# pcbsrc.net
KiCad netlist of a schematic drawn in EasyEDA Pro
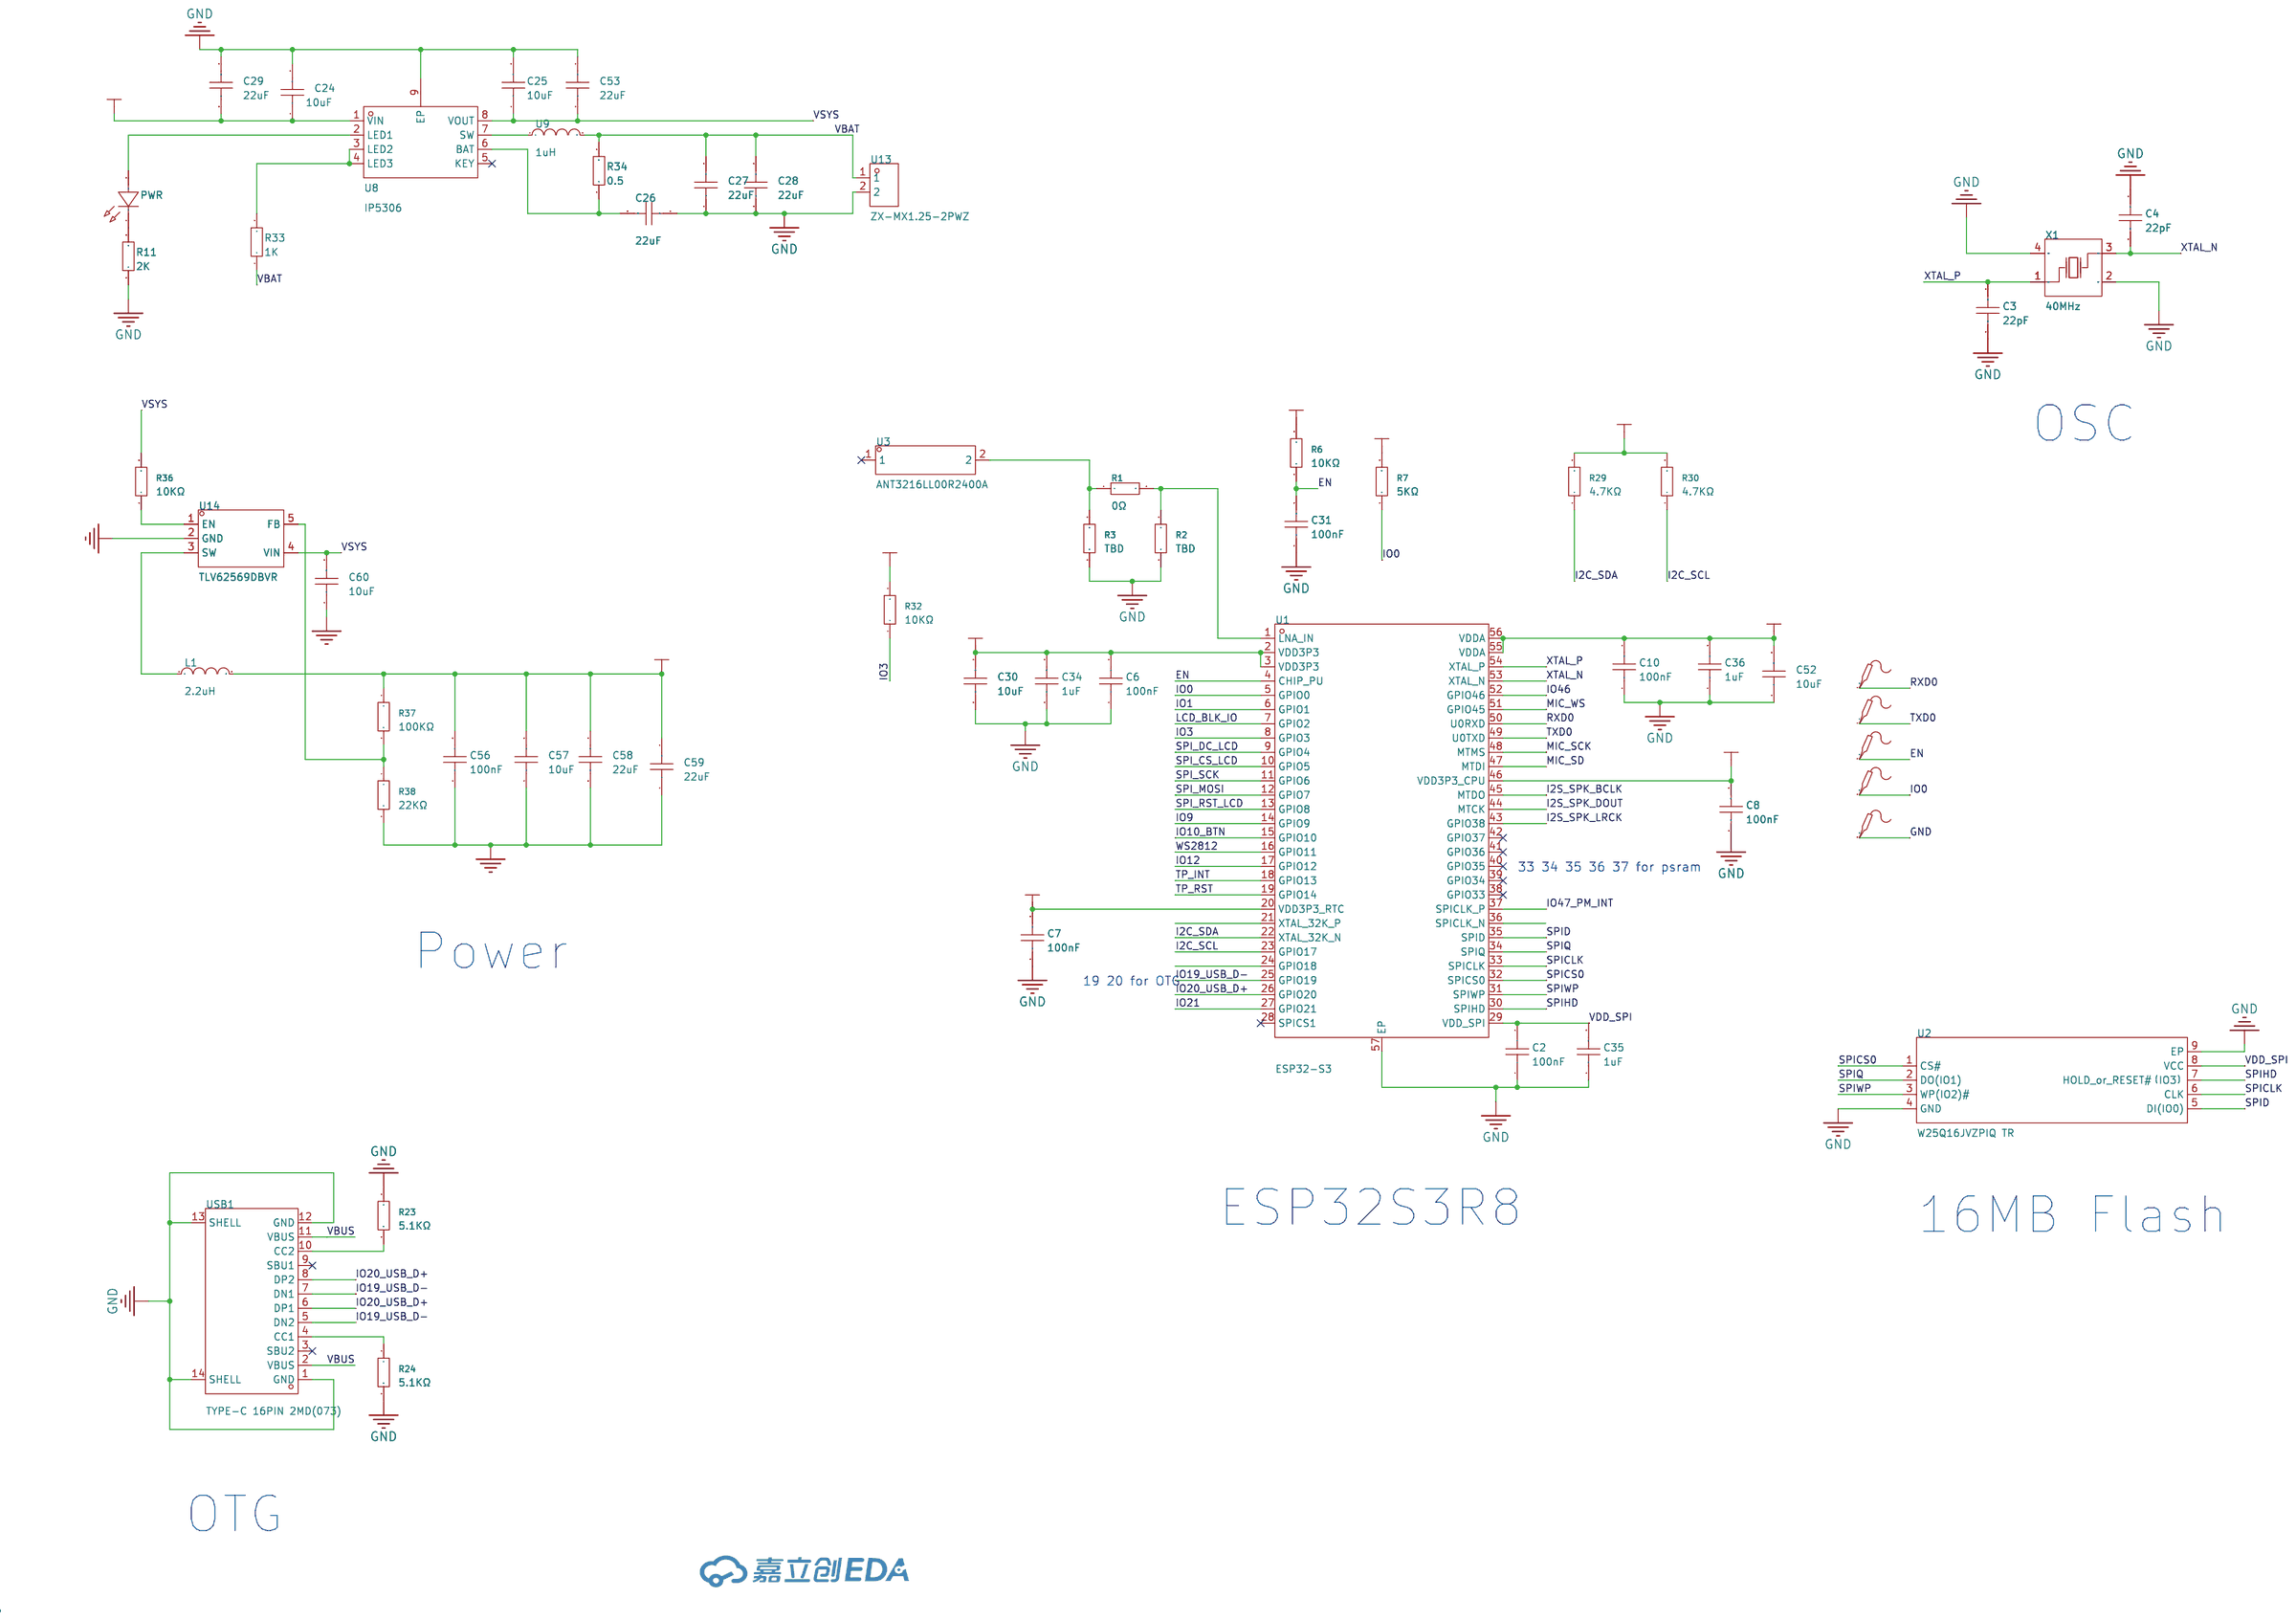
[diagram p0: esp32]
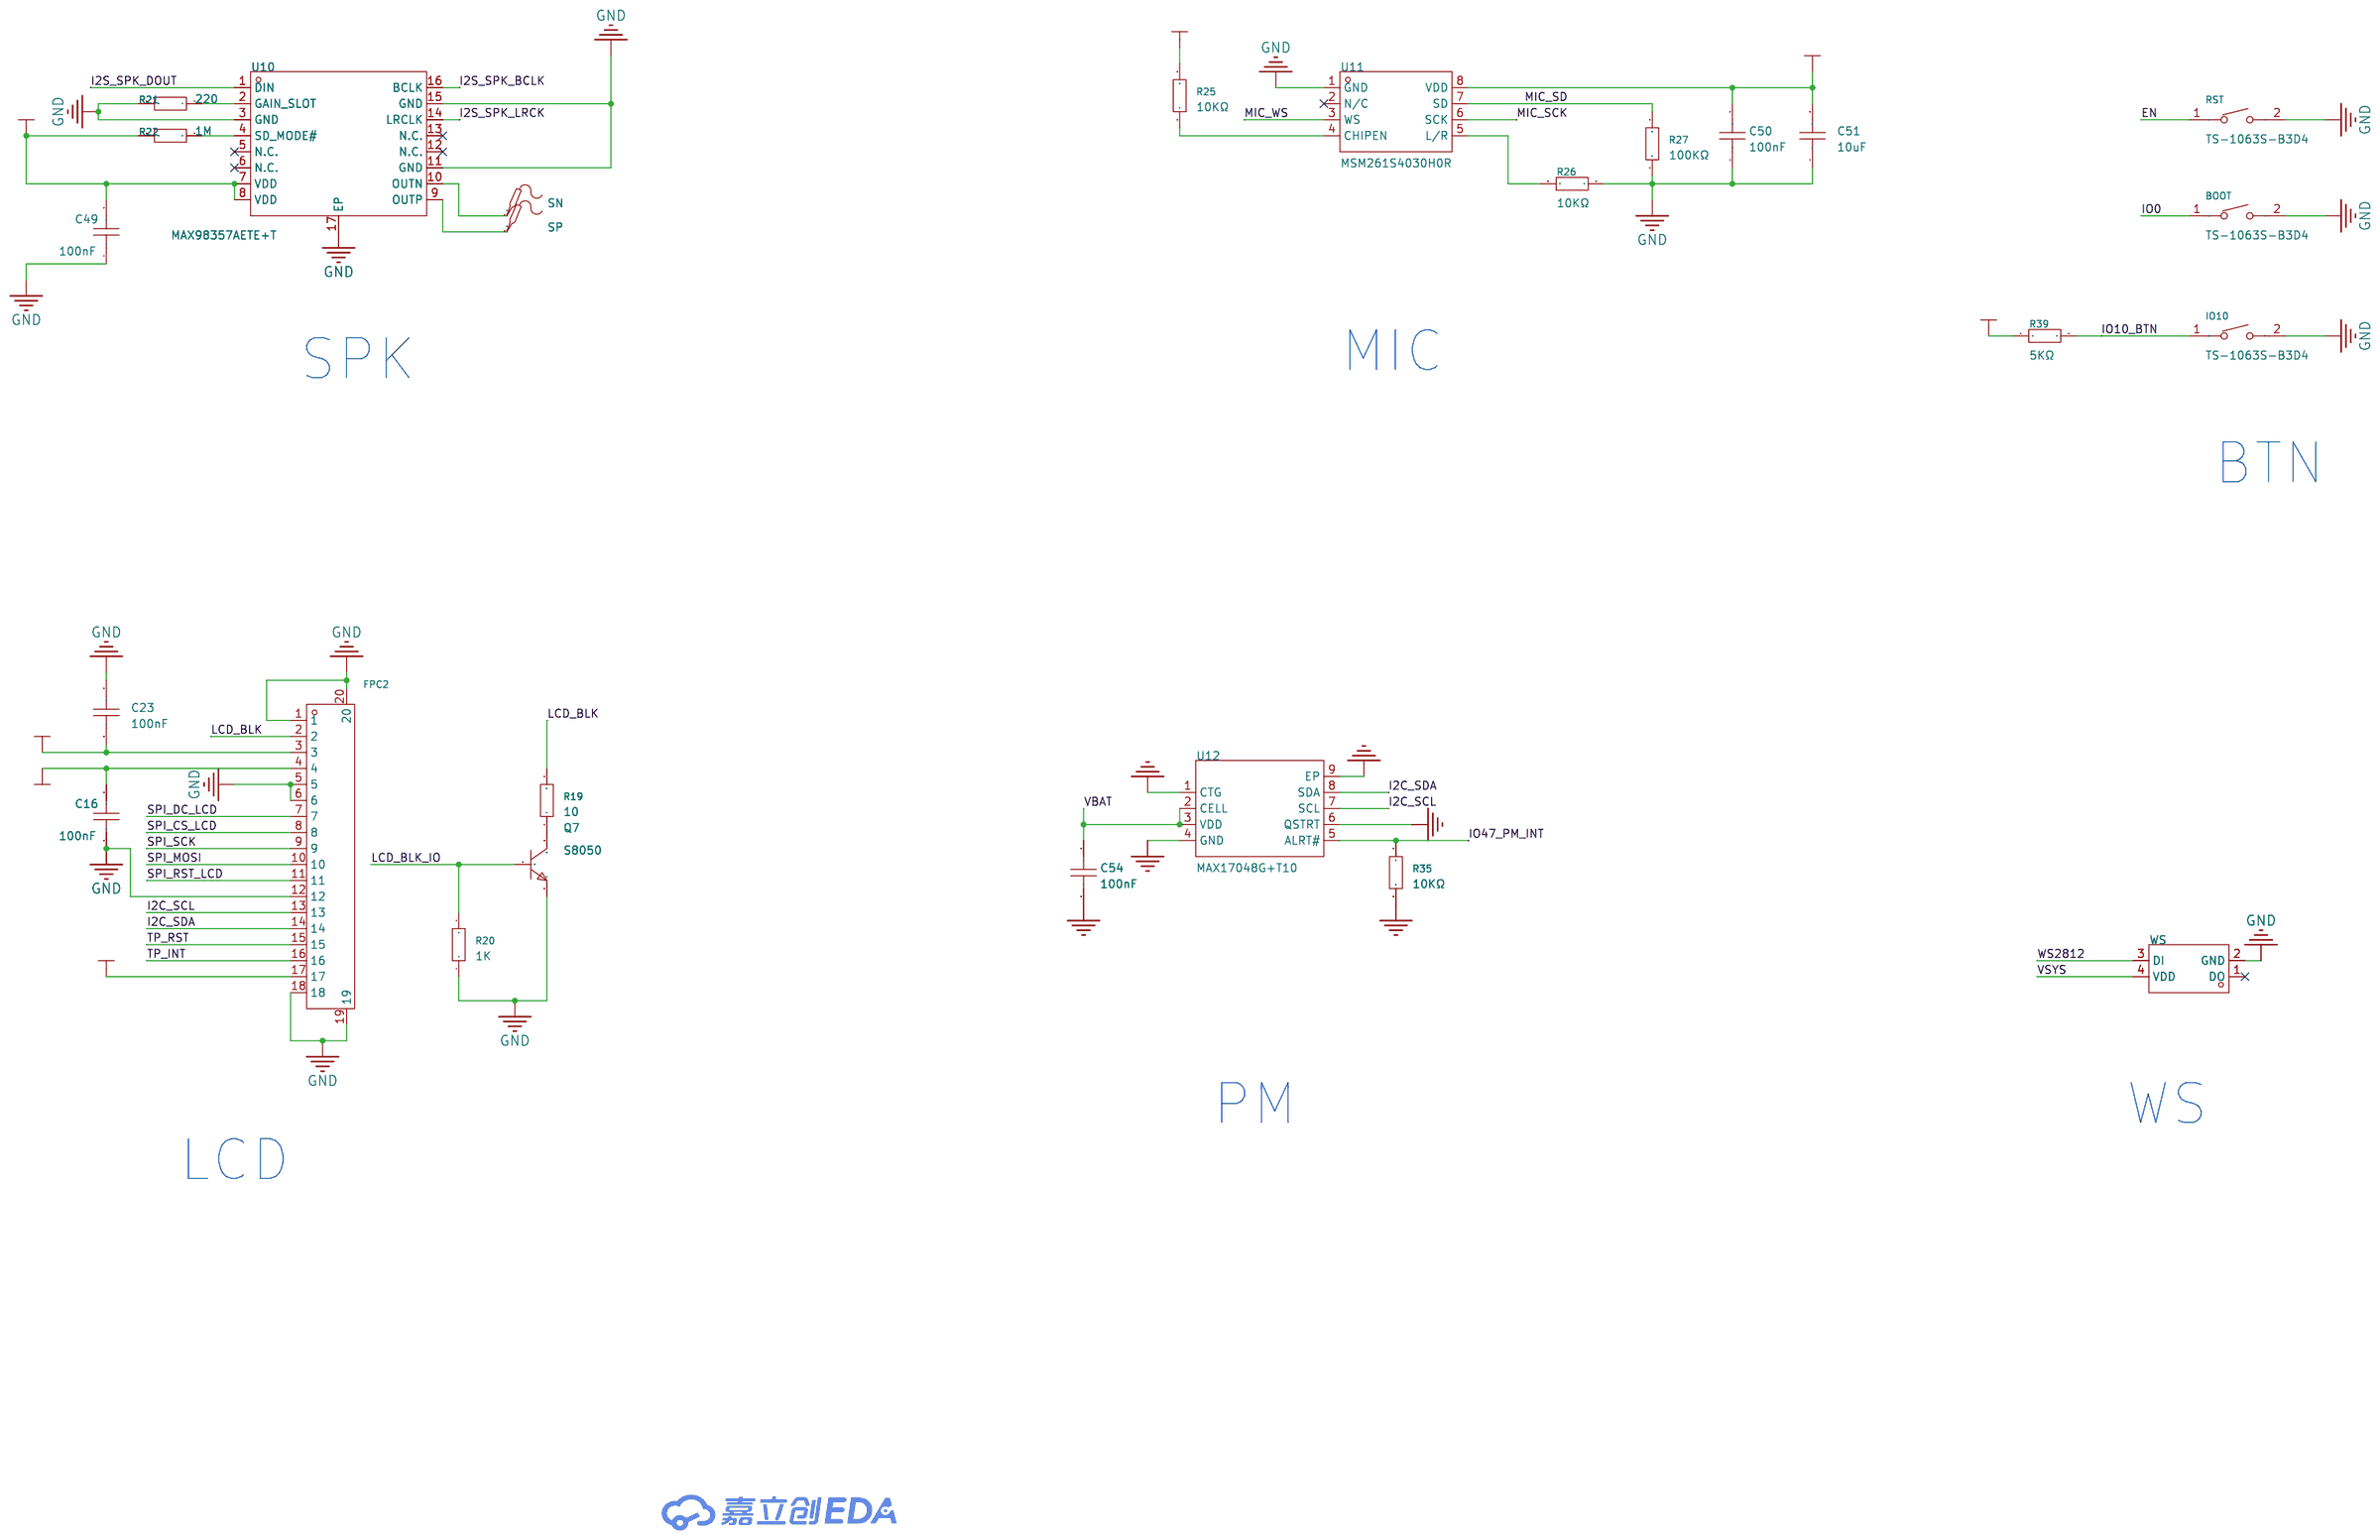
[diagram p1: peripheral]

(export (version "E")
  (design (tool "Eeschema 10.0.6"))
  (components
    (comp (ref "C2")
      (value "100nF")
      (footprint "easyedapro:C0402")
      (fields
        (field (name "Manufacturer Part") "CL05A105KA5NQNC")
        (field (name "Manufacturer") "SAMSUNG(三星)")
      )
      (libsource (lib "easyedapro") (part "CL05A105KA5NQNC"))
    )
    (comp (ref "C3")
      (value "22pF")
      (footprint "easyedapro:C0402")
      (fields
        (field (name "Manufacturer Part") "CL05A105KA5NQNC")
        (field (name "Manufacturer") "SAMSUNG(三星)")
      )
      (libsource (lib "easyedapro") (part "CL05A105KA5NQNC"))
    )
    (comp (ref "C4")
      (value "22pF")
      (footprint "easyedapro:C0402")
      (fields
        (field (name "Manufacturer Part") "CL05A105KA5NQNC")
        (field (name "Manufacturer") "SAMSUNG(三星)")
      )
      (libsource (lib "easyedapro") (part "CL05A105KA5NQNC"))
    )
    (comp (ref "C6")
      (value "100nF")
      (footprint "easyedapro:C0402")
      (fields
        (field (name "Manufacturer Part") "CL05A105KA5NQNC")
        (field (name "Manufacturer") "SAMSUNG(三星)")
      )
      (libsource (lib "easyedapro") (part "CL05A105KA5NQNC"))
    )
    (comp (ref "C7")
      (value "100nF")
      (footprint "easyedapro:C0402")
      (fields
        (field (name "Manufacturer Part") "CL05A105KA5NQNC")
        (field (name "Manufacturer") "SAMSUNG(三星)")
      )
      (libsource (lib "easyedapro") (part "CL05A105KA5NQNC"))
    )
    (comp (ref "C8")
      (value "100nF")
      (footprint "easyedapro:C0402")
      (fields
        (field (name "Manufacturer Part") "CL05A105KA5NQNC")
        (field (name "Manufacturer") "SAMSUNG(三星)")
      )
      (libsource (lib "easyedapro") (part "CL05A105KA5NQNC"))
    )
    (comp (ref "C10")
      (value "100nF")
      (footprint "easyedapro:C0402")
      (fields
        (field (name "Manufacturer Part") "CL05A105KA5NQNC")
        (field (name "Manufacturer") "SAMSUNG(三星)")
      )
      (libsource (lib "easyedapro") (part "CL05A105KA5NQNC"))
    )
    (comp (ref "C24")
      (value "10uF")
      (footprint "easyedapro:C0603")
      (description "容值:10uF;精度:±10%;额定电压:10V;材质(温度系数):X5R;")
      (fields
        (field (name "Manufacturer Part") "CGA0603X5R106K100JT")
        (field (name "Manufacturer") "HRE(芯声)")
      )
      (libsource (lib "easyedapro") (part "CGA0603X5R106K100JT"))
    )
    (comp (ref "C25")
      (value "10uF")
      (footprint "easyedapro:C0603")
      (description "容值:10uF;精度:±10%;额定电压:10V;材质(温度系数):X5R;")
      (fields
        (field (name "Manufacturer Part") "CGA0603X5R106K100JT")
        (field (name "Manufacturer") "HRE(芯声)")
      )
      (libsource (lib "easyedapro") (part "CGA0603X5R106K100JT"))
    )
    (comp (ref "C26")
      (value "22uF")
      (footprint "easyedapro:C0603")
      (description "容值:10uF;精度:±10%;额定电压:10V;材质(温度系数):X5R;")
      (fields
        (field (name "Manufacturer Part") "CGA0603X5R106K100JT")
        (field (name "Manufacturer") "HRE(芯声)")
      )
      (libsource (lib "easyedapro") (part "CGA0603X5R106K100JT"))
    )
    (comp (ref "C27")
      (value "22uF")
      (footprint "easyedapro:C0603")
      (description "容值:10uF;精度:±10%;额定电压:10V;材质(温度系数):X5R;")
      (fields
        (field (name "Manufacturer Part") "CGA0603X5R106K100JT")
        (field (name "Manufacturer") "HRE(芯声)")
      )
      (libsource (lib "easyedapro") (part "CGA0603X5R106K100JT"))
    )
    (comp (ref "C28")
      (value "22uF")
      (footprint "easyedapro:C0603")
      (description "容值:10uF;精度:±10%;额定电压:10V;材质(温度系数):X5R;")
      (fields
        (field (name "Manufacturer Part") "CGA0603X5R106K100JT")
        (field (name "Manufacturer") "HRE(芯声)")
      )
      (libsource (lib "easyedapro") (part "CGA0603X5R106K100JT"))
    )
    (comp (ref "C29")
      (value "22uF")
      (footprint "easyedapro:C0603")
      (description "容值:10uF;精度:±10%;额定电压:10V;材质(温度系数):X5R;")
      (fields
        (field (name "Manufacturer Part") "CGA0603X5R106K100JT")
        (field (name "Manufacturer") "HRE(芯声)")
      )
      (libsource (lib "easyedapro") (part "CGA0603X5R106K100JT"))
    )
    (comp (ref "C30")
      (value "10uF")
      (footprint "easyedapro:C0603")
      (description "Capacitance:10uF Tolerance:±10% Tolerance:±10% Voltage Rating:10V Temperature Coefficient:X5R")
      (fields
        (field (name "Manufacturer Part") "CGA0603X5R106K100JT")
        (field (name "Manufacturer") "HRE(芯声)")
      )
      (libsource (lib "") (part "CGA0603X5R106K100JT_1"))
    )
    (comp (ref "C31")
      (value "100nF")
      (footprint "easyedapro:C0402")
      (fields
        (field (name "Manufacturer Part") "CL05A105KA5NQNC")
        (field (name "Manufacturer") "SAMSUNG(三星)")
      )
      (libsource (lib "easyedapro") (part "CL05A105KA5NQNC"))
    )
    (comp (ref "C34")
      (value "1uF")
      (footprint "easyedapro:C0402")
      (fields
        (field (name "Manufacturer Part") "CL05A105KA5NQNC")
        (field (name "Manufacturer") "SAMSUNG(三星)")
      )
      (libsource (lib "easyedapro") (part "CL05A105KA5NQNC"))
    )
    (comp (ref "C35")
      (value "1uF")
      (footprint "easyedapro:C0402")
      (fields
        (field (name "Manufacturer Part") "CL05A105KA5NQNC")
        (field (name "Manufacturer") "SAMSUNG(三星)")
      )
      (libsource (lib "easyedapro") (part "CL05A105KA5NQNC"))
    )
    (comp (ref "C36")
      (value "1uF")
      (footprint "easyedapro:C0402")
      (fields
        (field (name "Manufacturer Part") "CL05A105KA5NQNC")
        (field (name "Manufacturer") "SAMSUNG(三星)")
      )
      (libsource (lib "easyedapro") (part "CL05A105KA5NQNC"))
    )
    (comp (ref "C52")
      (value "10uF")
      (footprint "easyedapro:C0603")
      (description "Capacitance:10uF Tolerance:±10% Tolerance:±10% Voltage Rating:10V Temperature Coefficient:X5R")
      (fields
        (field (name "Manufacturer Part") "CGA0603X5R106K100JT")
        (field (name "Manufacturer") "HRE(芯声)")
      )
      (libsource (lib "") (part "CGA0603X5R106K100JT_1"))
    )
    (comp (ref "C53")
      (value "22uF")
      (footprint "easyedapro:C0603")
      (description "容值:10uF;精度:±10%;额定电压:10V;材质(温度系数):X5R;")
      (fields
        (field (name "Manufacturer Part") "CGA0603X5R106K100JT")
        (field (name "Manufacturer") "HRE(芯声)")
      )
      (libsource (lib "easyedapro") (part "CGA0603X5R106K100JT"))
    )
    (comp (ref "C56")
      (value "100nF")
      (footprint "easyedapro:C0402")
      (fields
        (field (name "Manufacturer Part") "CL05A105KA5NQNC")
        (field (name "Manufacturer") "SAMSUNG(三星)")
      )
      (libsource (lib "easyedapro") (part "CL05A105KA5NQNC"))
    )
    (comp (ref "C57")
      (value "10uF")
      (footprint "easyedapro:C0603")
      (description "Capacitance:10uF Tolerance:±10% Tolerance:±10% Voltage Rating:10V Temperature Coefficient:X5R")
      (fields
        (field (name "Manufacturer Part") "CGA0603X5R106K100JT")
        (field (name "Manufacturer") "HRE(芯声)")
      )
      (libsource (lib "") (part "CGA0603X5R106K100JT_1"))
    )
    (comp (ref "C58")
      (value "22uF")
      (footprint "easyedapro:C0603")
      (description "容值:10uF;精度:±10%;额定电压:10V;材质(温度系数):X5R;")
      (fields
        (field (name "Manufacturer Part") "CGA0603X5R106K100JT")
        (field (name "Manufacturer") "HRE(芯声)")
      )
      (libsource (lib "easyedapro") (part "CGA0603X5R106K100JT"))
    )
    (comp (ref "C59")
      (value "22uF")
      (footprint "easyedapro:C0603")
      (description "容值:10uF;精度:±10%;额定电压:10V;材质(温度系数):X5R;")
      (fields
        (field (name "Manufacturer Part") "CGA0603X5R106K100JT")
        (field (name "Manufacturer") "HRE(芯声)")
      )
      (libsource (lib "easyedapro") (part "CGA0603X5R106K100JT"))
    )
    (comp (ref "C60")
      (value "10uF")
      (footprint "easyedapro:C0603")
      (description "Capacitance:10uF Tolerance:±10% Tolerance:±10% Voltage Rating:10V Temperature Coefficient:X5R")
      (fields
        (field (name "Manufacturer Part") "CGA0603X5R106K100JT")
        (field (name "Manufacturer") "HRE(芯声)")
      )
      (libsource (lib "") (part "CGA0603X5R106K100JT_1"))
    )
    (comp (ref "EN")
      (value "~")
      (footprint "easyedapro:Test-Point-0.5mm")
      (description "Test Point 测试点")
      (libsource (lib "easyedapro") (part "Test-Point"))
    )
    (comp (ref "IO0")
      (value "~")
      (footprint "easyedapro:Test-Point-0.5mm")
      (description "Test Point 测试点")
      (libsource (lib "easyedapro") (part "Test-Point"))
    )
    (comp (ref "IO11")
      (value "~")
      (footprint "easyedapro:Test-Point-0.5mm")
      (description "Test Point 测试点")
      (libsource (lib "easyedapro") (part "Test-Point"))
    )
    (comp (ref "L1")
      (value "2.2uH")
      (footprint "easyedapro:IND-SMD_L4.0-W4.0_LQH44PN2R2MP0L")
      (description "电感值:2.2uH;精度:±20%;额定电流:3.4A;饱和电流(Isat):3.4A;")
      (fields (field (name "Manufacturer Part") "SMNR4020-2.2UH") (field (name "Manufacturer") "SXN(顺翔诺)"))
      (libsource (lib "easyedapro") (part "SMNR4020-2.2UH"))
    )
    (comp (ref "PWR")
      (value "XL-1608SURC-06")
      (footprint "easyedapro:LED0603-RD_RED")
      (description "发光颜色:红色;功率:55mW;正向电流:25mA;主波长:617nm~621nm;透镜颜色:无色透明透镜;色温:-;发光角度:120°;载带方式:正贴;工作温度:-30°C~+85°C;")
      (fields (field (name "Manufacturer") "XINGLIGHT(成兴光)"))
      (libsource (lib "easyedapro") (part "XL-1608SURC-06"))
    )
    (comp (ref "R1")
      (value "0Ω")
      (footprint "easyedapro:R0402")
      (fields
        (field (name "Manufacturer Part") "0402WGF0000TCE")
        (field (name "Manufacturer") "UNI-ROYAL(厚声)")
      )
      (libsource (lib "easyedapro") (part "0402WGF0000TCE"))
    )
    (comp (ref "R2")
      (value "TBD")
      (footprint "easyedapro:R0402")
      (fields
        (field (name "Manufacturer Part") "0402WGF0000TCE")
        (field (name "Manufacturer") "UNI-ROYAL(厚声)")
      )
      (libsource (lib "easyedapro") (part "0402WGF0000TCE"))
    )
    (comp (ref "R3")
      (value "TBD")
      (footprint "easyedapro:R0402")
      (fields
        (field (name "Manufacturer Part") "0402WGF0000TCE")
        (field (name "Manufacturer") "UNI-ROYAL(厚声)")
      )
      (libsource (lib "easyedapro") (part "0402WGF0000TCE"))
    )
    (comp (ref "R6")
      (value "10KΩ")
      (footprint "easyedapro:R0402")
      (fields
        (field (name "Manufacturer Part") "0402WGF0000TCE")
        (field (name "Manufacturer") "UNI-ROYAL(厚声)")
      )
      (libsource (lib "easyedapro") (part "0402WGF0000TCE"))
    )
    (comp (ref "R7")
      (value "5KΩ")
      (footprint "easyedapro:R0402")
      (fields
        (field (name "Manufacturer Part") "0402WGF0000TCE")
        (field (name "Manufacturer") "UNI-ROYAL(厚声)")
      )
      (libsource (lib "easyedapro") (part "0402WGF0000TCE"))
    )
    (comp (ref "R11")
      (value "2K")
      (footprint "easyedapro:R0402")
      (description "电阻类型:厚膜电阻;阻值:470Ω;精度:±1%;功率:62.5mW;最大工作电压:50V;温度系数:±100ppm/°C;")
      (fields
        (field (name "Manufacturer Part") "0402WGF4700TCE")
        (field (name "Manufacturer") "UNI-ROYAL(厚声)")
      )
      (libsource (lib "easyedapro") (part "0402WGF4700TCE"))
    )
    (comp (ref "R23")
      (value "5.1KΩ")
      (footprint "easyedapro:R0402")
      (fields
        (field (name "Manufacturer Part") "0402WGF0000TCE")
        (field (name "Manufacturer") "UNI-ROYAL(厚声)")
      )
      (libsource (lib "easyedapro") (part "0402WGF0000TCE"))
    )
    (comp (ref "R24")
      (value "5.1KΩ")
      (footprint "easyedapro:R0402")
      (fields
        (field (name "Manufacturer Part") "0402WGF0000TCE")
        (field (name "Manufacturer") "UNI-ROYAL(厚声)")
      )
      (libsource (lib "easyedapro") (part "0402WGF0000TCE"))
    )
    (comp (ref "R29")
      (value "4.7KΩ")
      (footprint "easyedapro:R0402")
      (fields
        (field (name "Manufacturer Part") "0402WGF0000TCE")
        (field (name "Manufacturer") "UNI-ROYAL(厚声)")
      )
      (libsource (lib "easyedapro") (part "0402WGF0000TCE"))
    )
    (comp (ref "R30")
      (value "4.7KΩ")
      (footprint "easyedapro:R0402")
      (fields
        (field (name "Manufacturer Part") "0402WGF0000TCE")
        (field (name "Manufacturer") "UNI-ROYAL(厚声)")
      )
      (libsource (lib "easyedapro") (part "0402WGF0000TCE"))
    )
    (comp (ref "R32")
      (value "10KΩ")
      (footprint "easyedapro:R0402")
      (fields
        (field (name "Manufacturer Part") "0402WGF0000TCE")
        (field (name "Manufacturer") "UNI-ROYAL(厚声)")
      )
      (libsource (lib "easyedapro") (part "0402WGF0000TCE"))
    )
    (comp (ref "R33")
      (value "1K")
      (footprint "easyedapro:R0402")
      (description "电阻类型:厚膜电阻;阻值:470Ω;精度:±1%;功率:62.5mW;最大工作电压:50V;温度系数:±100ppm/°C;")
      (fields
        (field (name "Manufacturer Part") "0402WGF4700TCE")
        (field (name "Manufacturer") "UNI-ROYAL(厚声)")
      )
      (libsource (lib "easyedapro") (part "0402WGF4700TCE"))
    )
    (comp (ref "R34")
      (value "1K")
      (footprint "easyedapro:R0402")
      (description "电阻类型:厚膜电阻;阻值:470Ω;精度:±1%;功率:62.5mW;最大工作电压:50V;温度系数:±100ppm/°C;")
      (fields
        (field (name "Manufacturer Part") "0402WGF4700TCE")
        (field (name "Manufacturer") "UNI-ROYAL(厚声)")
      )
      (libsource (lib "easyedapro") (part "0402WGF4700TCE"))
    )
    (comp (ref "R36")
      (value "10KΩ")
      (footprint "easyedapro:R0402")
      (fields
        (field (name "Manufacturer Part") "0402WGF0000TCE")
        (field (name "Manufacturer") "UNI-ROYAL(厚声)")
      )
      (libsource (lib "easyedapro") (part "0402WGF0000TCE"))
    )
    (comp (ref "R37")
      (value "100KΩ")
      (footprint "easyedapro:R0402")
      (fields
        (field (name "Manufacturer Part") "0402WGF0000TCE")
        (field (name "Manufacturer") "UNI-ROYAL(厚声)")
      )
      (libsource (lib "easyedapro") (part "0402WGF0000TCE"))
    )
    (comp (ref "R38")
      (value "22KΩ")
      (footprint "easyedapro:R0402")
      (fields
        (field (name "Manufacturer Part") "0402WGF0000TCE")
        (field (name "Manufacturer") "UNI-ROYAL(厚声)")
      )
      (libsource (lib "easyedapro") (part "0402WGF0000TCE"))
    )
    (comp (ref "RXD0")
      (value "~")
      (footprint "easyedapro:Test-Point-0.5mm")
      (description "Test Point 测试点")
      (libsource (lib "easyedapro") (part "Test-Point"))
    )
    (comp (ref "TXD0")
      (value "~")
      (footprint "easyedapro:Test-Point-0.5mm")
      (description "Test Point 测试点")
      (libsource (lib "easyedapro") (part "Test-Point"))
    )
    (comp (ref "U1")
      (value "ESP32-S3")
      (footprint "easyedapro:QFN-56_L7.0-W7.0-P0.40-TL-EP4.0")
      (fields (field (name "Manufacturer") "ESPRESSIF(乐鑫)"))
      (libsource (lib "easyedapro") (part "ESP32-S3"))
    )
    (comp (ref "U2")
      (value "W25Q16JVZPIQ TR")
      (footprint "easyedapro:WSON-8_L6.0-W5.0-P1.27-BL-EP")
      (fields (field (name "Manufacturer") "WINBOND(华邦)"))
      (libsource (lib "easyedapro") (part "W25Q16JVZPIQ TR"))
    )
    (comp (ref "U3")
      (value "ANT3216LL00R2400A")
      (footprint "easyedapro:ANT-SMD_L3.2-W1.6")
      (fields (field (name "Manufacturer") "YAGEO(国巨)"))
      (libsource (lib "easyedapro") (part "ANT3216LL00R2400A"))
    )
    (comp (ref "U8")
      (value "IP5306")
      (footprint "easyedapro:ESOP-8_L4.9-W3.9-P1.27-LS6.0-BL-EP")
      (fields (field (name "Manufacturer") "INJOINIC(英集芯)"))
      (libsource (lib "easyedapro") (part "IP5306"))
    )
    (comp (ref "U9")
      (value "1uH")
      (footprint "easyedapro:IND-SMD_L2.5-W2.0_YXNAQ252010-3R3M")
      (fields (field (name "Manufacturer Part") "IND\\L2.5XW"))
      (libsource (lib "easyedapro") (part "IND{backslash}L2.5XW"))
    )
    (comp (ref "U13")
      (value "ZX-MX1.25-2PWZ")
      (footprint "easyedapro:CONN-TH_2P-P1.25_ZX-MX1.25-2PWZ")
      (fields (field (name "Manufacturer") "Megastar(兆星)"))
      (libsource (lib "easyedapro") (part "ZX-MX1.25-2PWZ"))
    )
    (comp (ref "U14")
      (value "TLV62569DBVR")
      (footprint "easyedapro:SOT-23-5_L3.0-W1.7-P0.95-LS2.8-BR")
      (description "功能类型:降压型;输出类型:可调;工作电压:2.5V~5.5V;输出电压:600mV~5.5V;输出电流:2A;")
      (fields (field (name "Manufacturer") "TI(德州仪器)"))
      (libsource (lib "easyedapro") (part "TLV62569DBVR"))
    )
    (comp (ref "USB1")
      (value "TYPE-C 16PIN 2MD(073)")
      (footprint "easyedapro:USB-C-SMD_TYPE-C-6PIN-2MD-073")
      (fields (field (name "Manufacturer") "SHOU HAN(首韩)"))
      (libsource (lib "easyedapro") (part "TYPE-C 16PIN 2MD(073)"))
    )
    (comp (ref "X1")
      (value "40MHz")
      (footprint "easyedapro:OSC-SMD_4P-L3.2-W2.5-BL_SIT8008BI")
      (fields (field (name "Manufacturer Part") "X322540MPB4SI") (field (name "Manufacturer") "YXC(扬兴晶振)"))
      (libsource (lib "easyedapro") (part "X322540MPB4SI"))
    )
    (comp (ref "BOOT")
      (value "TS-1063S-B3D4")
      (footprint "easyedapro:KEY-SMD_L3.0-W2.5-LS4.0_TS-1603S")
      (fields (field (name "Manufacturer") "Yuandi(元迪)"))
      (libsource (lib "easyedapro") (part "TS-1063S-B3D4"))
    )
    (comp (ref "C16")
      (value "100nF")
      (footprint "easyedapro:C0402")
      (fields
        (field (name "Manufacturer Part") "CL05B104KO5NNNC")
        (field (name "Manufacturer") "SAMSUNG(三星)")
      )
      (libsource (lib "easyedapro") (part "CL05B104KO5NNNC"))
    )
    (comp (ref "C23")
      (value "100nF")
      (footprint "easyedapro:C0402")
      (fields
        (field (name "Manufacturer Part") "CL05B104KO5NNNC")
        (field (name "Manufacturer") "SAMSUNG(三星)")
      )
      (libsource (lib "easyedapro") (part "CL05B104KO5NNNC"))
    )
    (comp (ref "C49")
      (value "100nF")
      (footprint "easyedapro:C0402")
      (fields
        (field (name "Manufacturer Part") "CL05B104KO5NNNC")
        (field (name "Manufacturer") "SAMSUNG(三星)")
      )
      (libsource (lib "easyedapro") (part "CL05B104KO5NNNC"))
    )
    (comp (ref "C50")
      (value "100nF")
      (footprint "easyedapro:C0402")
      (fields
        (field (name "Manufacturer Part") "CL05A105KA5NQNC")
        (field (name "Manufacturer") "SAMSUNG(三星)")
      )
      (libsource (lib "easyedapro") (part "CL05A105KA5NQNC"))
    )
    (comp (ref "C51")
      (value "10uF")
      (footprint "easyedapro:C0603")
      (description "Capacitance:10uF Tolerance:±10% Tolerance:±10% Voltage Rating:10V Temperature Coefficient:X5R")
      (fields
        (field (name "Manufacturer Part") "CGA0603X5R106K100JT")
        (field (name "Manufacturer") "HRE(芯声)")
      )
      (libsource (lib "easyedapro") (part "CGA0603X5R106K100JT"))
    )
    (comp (ref "C54")
      (value "100nF")
      (footprint "easyedapro:C0402")
      (fields
        (field (name "Manufacturer Part") "CL05A105KA5NQNC")
        (field (name "Manufacturer") "SAMSUNG(三星)")
      )
      (libsource (lib "easyedapro") (part "CL05A105KA5NQNC"))
    )
    (comp (ref "FPC2")
      (value "FPC-05F-18PH20")
      (footprint "easyedapro:FPC-SMD_18P-P0.50_FPC-05F-18PH20")
      (fields (field (name "Manufacturer") "XUNPU(讯普)"))
      (libsource (lib "easyedapro") (part "FPC-05F-18PH20"))
    )
    (comp (ref "IO10")
      (value "TS-1063S-B3D4")
      (footprint "easyedapro:KEY-SMD_L3.0-W2.5-LS4.0_TS-1603S")
      (fields (field (name "Manufacturer") "Yuandi(元迪)"))
      (libsource (lib "easyedapro") (part "TS-1063S-B3D4"))
    )
    (comp (ref "Q7")
      (value "S8050")
      (footprint "easyedapro:SOT-23-3_L2.9-W1.3-P1.90-LS2.3-BR")
      (fields (field (name "Manufacturer") "宏嘉诚"))
      (libsource (lib "easyedapro") (part "S8050_C20069125"))
    )
    (comp (ref "R19")
      (value "10")
      (footprint "easyedapro:R0402")
      (fields
        (field (name "Manufacturer Part") "0402WGF4700TCE")
        (field (name "Manufacturer") "UNI-ROYAL(厚声)")
      )
      (libsource (lib "easyedapro") (part "0402WGF4700TCE"))
    )
    (comp (ref "R20")
      (value "1K")
      (footprint "easyedapro:R0402")
      (fields
        (field (name "Manufacturer Part") "0402WGF4700TCE")
        (field (name "Manufacturer") "UNI-ROYAL(厚声)")
      )
      (libsource (lib "easyedapro") (part "0402WGF4700TCE"))
    )
    (comp (ref "R21")
      (value "220")
      (footprint "easyedapro:R0402")
      (fields
        (field (name "Manufacturer Part") "0402WGF4700TCE")
        (field (name "Manufacturer") "UNI-ROYAL(厚声)")
      )
      (libsource (lib "easyedapro") (part "0402WGF4700TCE"))
    )
    (comp (ref "R22")
      (value "1M")
      (footprint "easyedapro:R0402")
      (fields
        (field (name "Manufacturer Part") "0402WGF4700TCE")
        (field (name "Manufacturer") "UNI-ROYAL(厚声)")
      )
      (libsource (lib "easyedapro") (part "0402WGF4700TCE"))
    )
    (comp (ref "R25")
      (value "10KΩ")
      (footprint "easyedapro:R0402")
      (fields
        (field (name "Manufacturer Part") "0402WGF0000TCE")
        (field (name "Manufacturer") "UNI-ROYAL(厚声)")
      )
      (libsource (lib "easyedapro") (part "0402WGF0000TCE"))
    )
    (comp (ref "R26")
      (value "10KΩ")
      (footprint "easyedapro:R0402")
      (fields
        (field (name "Manufacturer Part") "0402WGF0000TCE")
        (field (name "Manufacturer") "UNI-ROYAL(厚声)")
      )
      (libsource (lib "easyedapro") (part "0402WGF0000TCE"))
    )
    (comp (ref "R27")
      (value "100KΩ")
      (footprint "easyedapro:R0402")
      (fields
        (field (name "Manufacturer Part") "0402WGF0000TCE")
        (field (name "Manufacturer") "UNI-ROYAL(厚声)")
      )
      (libsource (lib "easyedapro") (part "0402WGF0000TCE"))
    )
    (comp (ref "R35")
      (value "10KΩ")
      (footprint "easyedapro:R0402")
      (fields
        (field (name "Manufacturer Part") "0402WGF0000TCE")
        (field (name "Manufacturer") "UNI-ROYAL(厚声)")
      )
      (libsource (lib "easyedapro") (part "0402WGF0000TCE"))
    )
    (comp (ref "R39")
      (value "5KΩ")
      (footprint "easyedapro:R0402")
      (fields
        (field (name "Manufacturer Part") "0402WGF0000TCE")
        (field (name "Manufacturer") "UNI-ROYAL(厚声)")
      )
      (libsource (lib "easyedapro") (part "0402WGF0000TCE"))
    )
    (comp (ref "RST")
      (value "TS-1063S-B3D4")
      (footprint "easyedapro:KEY-SMD_L3.0-W2.5-LS4.0_TS-1603S")
      (fields (field (name "Manufacturer") "Yuandi(元迪)"))
      (libsource (lib "easyedapro") (part "TS-1063S-B3D4"))
    )
    (comp (ref "SN")
      (value "~")
      (footprint "easyedapro:Test-Point-0.5mm")
      (description "Test Point 测试点")
      (libsource (lib "easyedapro") (part "Test-Point"))
    )
    (comp (ref "SP")
      (value "~")
      (footprint "easyedapro:Test-Point-0.5mm")
      (description "Test Point 测试点")
      (libsource (lib "easyedapro") (part "Test-Point"))
    )
    (comp (ref "U10")
      (value "MAX98357AETE+T")
      (footprint "easyedapro:TQFN-16_L3.0-W3.0-P0.50-BL-EP1.5")
      (fields (field (name "Manufacturer") "ADI(亚德诺)/MAXIM(美信)"))
      (libsource (lib "easyedapro") (part "MAX98357AETE+T"))
    )
    (comp (ref "U11")
      (value "MSM261S4030H0R")
      (footprint "easyedapro:MIC-SMD_8P-L4.0-W3.0-P1.00-BR")
      (fields (field (name "Manufacturer") "MEMS(敏芯微)"))
      (libsource (lib "easyedapro") (part "MSM261S4030H0R"))
    )
    (comp (ref "U12")
      (value "MAX17048G+T10")
      (footprint "easyedapro:TDFN-8_L2.0-W2.0-P0.50-BL-EP1.2")
      (description "工作电压:2.5V~4.5V;电池类型:锂离子/聚合物;电池节数:1;")
      (fields (field (name "Manufacturer") "ADI(亚德诺)/MAXIM(美信)"))
      (libsource (lib "easyedapro") (part "MAX17048G+T10"))
    )
    (comp (ref "WS")
      (value "XL-2020RGBC-WS2812B")
      (footprint "easyedapro:LED-SMD_4P-L2.0-W2.0-BR-1")
      (fields (field (name "Manufacturer") "XINGLIGHT(成兴光)"))
      (libsource (lib "easyedapro") (part "XL-2020RGBC-WS2812B"))
    )
  )
  (nets
    (net (code "1") (name "EN") (class "Default")
      (node (ref "C31") (pin "2") (pinfunction "2_2") (pintype "unspecified"))
      (node (ref "EN") (pin "1") (pinfunction "1_1") (pintype "input"))
      (node (ref "R6") (pin "1") (pinfunction "1_1") (pintype "input"))
      (node (ref "RST") (pin "1") (pinfunction "1_1") (pintype "input"))
      (node (ref "U1") (pin "4") (pinfunction "CHIP_PU_4") (pintype "unspecified"))
    )
    (net (code "2") (name "GND") (class "Default")
      (node (ref "BOOT") (pin "2") (pinfunction "2_2") (pintype "input"))
      (node (ref "C10") (pin "1") (pinfunction "1_1") (pintype "unspecified"))
      (node (ref "C16") (pin "1") (pinfunction "1_1") (pintype "unspecified"))
      (node (ref "C2") (pin "1") (pinfunction "1_1") (pintype "unspecified"))
      (node (ref "C23") (pin "1") (pinfunction "1_1") (pintype "unspecified"))
      (node (ref "C24") (pin "2") (pinfunction "2_2") (pintype "unspecified"))
      (node (ref "C25") (pin "2") (pinfunction "2_2") (pintype "unspecified"))
      (node (ref "C26") (pin "1") (pinfunction "1_1") (pintype "unspecified"))
      (node (ref "C27") (pin "2") (pinfunction "2_2") (pintype "unspecified"))
      (node (ref "C28") (pin "2") (pinfunction "2_2") (pintype "unspecified"))
      (node (ref "C29") (pin "1") (pinfunction "1_1") (pintype "unspecified"))
      (node (ref "C3") (pin "1") (pinfunction "1_1") (pintype "unspecified"))
      (node (ref "C30") (pin "1") (pinfunction "1_1") (pintype "unspecified"))
      (node (ref "C31") (pin "1") (pinfunction "1_1") (pintype "unspecified"))
      (node (ref "C34") (pin "1") (pinfunction "1_1") (pintype "unspecified"))
      (node (ref "C35") (pin "1") (pinfunction "1_1") (pintype "unspecified"))
      (node (ref "C36") (pin "1") (pinfunction "1_1") (pintype "unspecified"))
      (node (ref "C4") (pin "2") (pinfunction "2_2") (pintype "unspecified"))
      (node (ref "C49") (pin "1") (pinfunction "1_1") (pintype "unspecified"))
      (node (ref "C50") (pin "1") (pinfunction "1_1") (pintype "unspecified"))
      (node (ref "C51") (pin "1") (pinfunction "1_1") (pintype "unspecified"))
      (node (ref "C52") (pin "1") (pinfunction "1_1") (pintype "unspecified"))
      (node (ref "C53") (pin "1") (pinfunction "1_1") (pintype "unspecified"))
      (node (ref "C54") (pin "1") (pinfunction "1_1") (pintype "unspecified"))
      (node (ref "C56") (pin "1") (pinfunction "1_1") (pintype "unspecified"))
      (node (ref "C57") (pin "1") (pinfunction "1_1") (pintype "unspecified"))
      (node (ref "C58") (pin "2") (pinfunction "2_2") (pintype "unspecified"))
      (node (ref "C59") (pin "2") (pinfunction "2_2") (pintype "unspecified"))
      (node (ref "C6") (pin "1") (pinfunction "1_1") (pintype "unspecified"))
      (node (ref "C60") (pin "1") (pinfunction "1_1") (pintype "unspecified"))
      (node (ref "C7") (pin "1") (pinfunction "1_1") (pintype "unspecified"))
      (node (ref "C8") (pin "1") (pinfunction "1_1") (pintype "unspecified"))
      (node (ref "FPC2") (pin "1") (pinfunction "1_1") (pintype "input"))
      (node (ref "FPC2") (pin "12") (pinfunction "12_12") (pintype "input"))
      (node (ref "FPC2") (pin "18") (pinfunction "18_18") (pintype "input"))
      (node (ref "FPC2") (pin "19") (pinfunction "19_19") (pintype "input"))
      (node (ref "FPC2") (pin "20") (pinfunction "20_20") (pintype "input"))
      (node (ref "FPC2") (pin "5") (pinfunction "5_5") (pintype "input"))
      (node (ref "FPC2") (pin "6") (pinfunction "6_6") (pintype "input"))
      (node (ref "IO10") (pin "2") (pinfunction "2_2") (pintype "input"))
      (node (ref "IO11") (pin "1") (pinfunction "1_1") (pintype "input"))
      (node (ref "Q7") (pin "2") (pinfunction "E_2") (pintype "input"))
      (node (ref "R11") (pin "1") (pinfunction "1_1") (pintype "input"))
      (node (ref "R2") (pin "1") (pinfunction "1_1") (pintype "input"))
      (node (ref "R20") (pin "1") (pinfunction "1_1") (pintype "input"))
      (node (ref "R21") (pin "2") (pinfunction "2_2") (pintype "input"))
      (node (ref "R23") (pin "1") (pinfunction "1_1") (pintype "input"))
      (node (ref "R24") (pin "2") (pinfunction "2_2") (pintype "input"))
      (node (ref "R26") (pin "1") (pinfunction "1_1") (pintype "input"))
      (node (ref "R27") (pin "2") (pinfunction "2_2") (pintype "input"))
      (node (ref "R3") (pin "1") (pinfunction "1_1") (pintype "input"))
      (node (ref "R35") (pin "2") (pinfunction "2_2") (pintype "input"))
      (node (ref "R38") (pin "2") (pinfunction "2_2") (pintype "input"))
      (node (ref "RST") (pin "2") (pinfunction "2_2") (pintype "input"))
      (node (ref "U1") (pin "57") (pinfunction "EP_57") (pintype "unspecified"))
      (node (ref "U10") (pin "11") (pinfunction "GND_11") (pintype "unspecified"))
      (node (ref "U10") (pin "15") (pinfunction "GND_15") (pintype "unspecified"))
      (node (ref "U10") (pin "17") (pinfunction "EP_17") (pintype "unspecified"))
      (node (ref "U10") (pin "3") (pinfunction "GND_3") (pintype "unspecified"))
      (node (ref "U11") (pin "1") (pinfunction "GND_1") (pintype "unspecified"))
      (node (ref "U12") (pin "1") (pinfunction "CTG_1") (pintype "unspecified"))
      (node (ref "U12") (pin "4") (pinfunction "GND_4") (pintype "unspecified"))
      (node (ref "U12") (pin "6") (pinfunction "QSTRT_6") (pintype "unspecified"))
      (node (ref "U12") (pin "9") (pinfunction "EP_9") (pintype "unspecified"))
      (node (ref "U13") (pin "2") (pinfunction "2_2") (pintype "unspecified"))
      (node (ref "U14") (pin "2") (pinfunction "GND_2") (pintype "unspecified"))
      (node (ref "U2") (pin "4") (pinfunction "GND_4") (pintype "unspecified"))
      (node (ref "U2") (pin "9") (pinfunction "EP_9") (pintype "unspecified"))
      (node (ref "U8") (pin "9") (pinfunction "EP_9") (pintype "unspecified"))
      (node (ref "USB1") (pin "1") (pinfunction "GND_1") (pintype "unspecified"))
      (node (ref "USB1") (pin "12") (pinfunction "GND_12") (pintype "unspecified"))
      (node (ref "USB1") (pin "13") (pinfunction "SHELL_13") (pintype "unspecified"))
      (node (ref "USB1") (pin "14") (pinfunction "SHELL_14") (pintype "unspecified"))
      (node (ref "WS") (pin "2") (pinfunction "GND_2") (pintype "unspecified"))
      (node (ref "X1") (pin "2") (pinfunction "GND_2") (pintype "unspecified"))
      (node (ref "X1") (pin "4") (pinfunction "GND_4") (pintype "unspecified"))
    )
    (net (code "3") (name "I2C_SCL") (class "Default")
      (node (ref "FPC2") (pin "13") (pinfunction "13_13") (pintype "input"))
      (node (ref "R30") (pin "1") (pinfunction "1_1") (pintype "input"))
      (node (ref "U1") (pin "23") (pinfunction "GPIO17_23") (pintype "unspecified"))
      (node (ref "U12") (pin "7") (pinfunction "SCL_7") (pintype "unspecified"))
    )
    (net (code "4") (name "I2C_SDA") (class "Default")
      (node (ref "FPC2") (pin "14") (pinfunction "14_14") (pintype "input"))
      (node (ref "R29") (pin "1") (pinfunction "1_1") (pintype "input"))
      (node (ref "U1") (pin "22") (pinfunction "XTAL_32K_N_22") (pintype "unspecified"))
      (node (ref "U12") (pin "8") (pinfunction "SDA_8") (pintype "unspecified"))
    )
    (net (code "5") (name "I2S_SPK_BCLK") (class "Default")
      (node (ref "U1") (pin "45") (pinfunction "MTDO_45") (pintype "unspecified"))
      (node (ref "U10") (pin "16") (pinfunction "BCLK_16") (pintype "unspecified"))
    )
    (net (code "6") (name "I2S_SPK_DOUT") (class "Default")
      (node (ref "U1") (pin "44") (pinfunction "MTCK_44") (pintype "unspecified"))
      (node (ref "U10") (pin "1") (pinfunction "DIN_1") (pintype "unspecified"))
    )
    (net (code "7") (name "I2S_SPK_LRCK") (class "Default")
      (node (ref "U1") (pin "43") (pinfunction "GPIO38_43") (pintype "unspecified"))
      (node (ref "U10") (pin "14") (pinfunction "LRCLK_14") (pintype "unspecified"))
    )
    (net (code "8") (name "IO0") (class "Default")
      (node (ref "BOOT") (pin "1") (pinfunction "1_1") (pintype "input"))
      (node (ref "IO0") (pin "1") (pinfunction "1_1") (pintype "input"))
      (node (ref "R7") (pin "1") (pinfunction "1_1") (pintype "input"))
      (node (ref "U1") (pin "5") (pinfunction "GPIO0_5") (pintype "unspecified"))
    )
    (net (code "9") (name "IO1") (class "Default")
      (node (ref "U1") (pin "6") (pinfunction "GPIO1_6") (pintype "unspecified"))
    )
    (net (code "10") (name "IO3") (class "Default")
      (node (ref "R32") (pin "1") (pinfunction "1_1") (pintype "input"))
      (node (ref "U1") (pin "8") (pinfunction "GPIO3_8") (pintype "unspecified"))
    )
    (net (code "11") (name "IO9") (class "Default")
      (node (ref "U1") (pin "14") (pinfunction "GPIO9_14") (pintype "unspecified"))
    )
    (net (code "12") (name "IO10_BTN") (class "Default")
      (node (ref "IO10") (pin "1") (pinfunction "1_1") (pintype "input"))
      (node (ref "R39") (pin "1") (pinfunction "1_1") (pintype "input"))
      (node (ref "U1") (pin "15") (pinfunction "GPIO10_15") (pintype "unspecified"))
    )
    (net (code "13") (name "IO12") (class "Default")
      (node (ref "U1") (pin "17") (pinfunction "GPIO12_17") (pintype "unspecified"))
    )
    (net (code "14") (name "IO19_USB_D-") (class "Default")
      (node (ref "U1") (pin "25") (pinfunction "GPIO19_25") (pintype "unspecified"))
      (node (ref "USB1") (pin "5") (pinfunction "DN2_5") (pintype "unspecified"))
      (node (ref "USB1") (pin "7") (pinfunction "DN1_7") (pintype "unspecified"))
    )
    (net (code "15") (name "IO20_USB_D+") (class "Default")
      (node (ref "U1") (pin "26") (pinfunction "GPIO20_26") (pintype "unspecified"))
      (node (ref "USB1") (pin "6") (pinfunction "DP1_6") (pintype "unspecified"))
      (node (ref "USB1") (pin "8") (pinfunction "DP2_8") (pintype "unspecified"))
    )
    (net (code "16") (name "IO21") (class "Default")
      (node (ref "U1") (pin "27") (pinfunction "GPIO21_27") (pintype "unspecified"))
    )
    (net (code "17") (name "IO46") (class "Default")
      (node (ref "U1") (pin "52") (pinfunction "GPIO46_52") (pintype "unspecified"))
    )
    (net (code "18") (name "IO47_PM_INT") (class "Default")
      (node (ref "R35") (pin "1") (pinfunction "1_1") (pintype "input"))
      (node (ref "U1") (pin "37") (pinfunction "SPICLK_P_37") (pintype "unspecified"))
      (node (ref "U12") (pin "5") (pinfunction "ALRT#_5") (pintype "unspecified"))
    )
    (net (code "19") (name "LCD_BLK") (class "Default")
      (node (ref "FPC2") (pin "2") (pinfunction "2_2") (pintype "input"))
      (node (ref "R19") (pin "2") (pinfunction "2_2") (pintype "input"))
    )
    (net (code "20") (name "LCD_BLK_IO") (class "Default")
      (node (ref "Q7") (pin "1") (pinfunction "B_1") (pintype "input"))
      (node (ref "R20") (pin "2") (pinfunction "2_2") (pintype "input"))
      (node (ref "U1") (pin "7") (pinfunction "GPIO2_7") (pintype "unspecified"))
    )
    (net (code "21") (name "MIC_SCK") (class "Default")
      (node (ref "U1") (pin "48") (pinfunction "MTMS_48") (pintype "unspecified"))
      (node (ref "U11") (pin "6") (pinfunction "SCK_6") (pintype "unspecified"))
    )
    (net (code "22") (name "MIC_SD") (class "Default")
      (node (ref "R27") (pin "1") (pinfunction "1_1") (pintype "input"))
      (node (ref "U1") (pin "47") (pinfunction "MTDI_47") (pintype "unspecified"))
      (node (ref "U11") (pin "7") (pinfunction "SD_7") (pintype "unspecified"))
    )
    (net (code "23") (name "MIC_WS") (class "Default")
      (node (ref "U1") (pin "51") (pinfunction "GPIO45_51") (pintype "unspecified"))
      (node (ref "U11") (pin "3") (pinfunction "WS_3") (pintype "unspecified"))
    )
    (net (code "24") (name "Net-(PWR-A)") (class "Default")
      (node (ref "PWR") (pin "2") (pinfunction "A_2") (pintype "unspecified"))
      (node (ref "U8") (pin "2") (pinfunction "LED1_2") (pintype "unspecified"))
    )
    (net (code "25") (name "Net-(PWR-K)") (class "Default")
      (node (ref "PWR") (pin "1") (pinfunction "K_1") (pintype "unspecified"))
      (node (ref "R11") (pin "2") (pinfunction "2_2") (pintype "input"))
    )
    (net (code "26") (name "Net-(Q7-C)") (class "Default")
      (node (ref "Q7") (pin "3") (pinfunction "C_3") (pintype "input"))
      (node (ref "R19") (pin "1") (pinfunction "1_1") (pintype "input"))
    )
    (net (code "27") (name "Net-(R1-Pad1)") (class "Default")
      (node (ref "R1") (pin "1") (pinfunction "1_1") (pintype "input"))
      (node (ref "R3") (pin "2") (pinfunction "2_2") (pintype "input"))
      (node (ref "U3") (pin "2") (pinfunction "2_2") (pintype "unspecified"))
    )
    (net (code "28") (name "Net-(U1-LNA_IN)") (class "Default")
      (node (ref "R1") (pin "2") (pinfunction "2_2") (pintype "input"))
      (node (ref "R2") (pin "2") (pinfunction "2_2") (pintype "input"))
      (node (ref "U1") (pin "1") (pinfunction "LNA_IN_1") (pintype "unspecified"))
    )
    (net (code "29") (name "Net-(U8-BAT)") (class "Default")
      (node (ref "C26") (pin "2") (pinfunction "2_2") (pintype "unspecified"))
      (node (ref "R34") (pin "1") (pinfunction "1_1") (pintype "input"))
      (node (ref "U8") (pin "6") (pinfunction "BAT_6") (pintype "unspecified"))
    )
    (net (code "30") (name "Net-(U8-LED2)") (class "Default")
      (node (ref "R33") (pin "2") (pinfunction "2_2") (pintype "input"))
      (node (ref "U8") (pin "3") (pinfunction "LED2_3") (pintype "unspecified"))
      (node (ref "U8") (pin "4") (pinfunction "LED3_4") (pintype "unspecified"))
    )
    (net (code "31") (name "Net-(U8-SW)") (class "Default")
      (node (ref "U8") (pin "7") (pinfunction "SW_7") (pintype "unspecified"))
      (node (ref "U9") (pin "1") (pinfunction "1_1") (pintype "unspecified"))
    )
    (net (code "32") (name "Net-(U10-GAIN_SLOT)") (class "Default")
      (node (ref "R21") (pin "1") (pinfunction "1_1") (pintype "input"))
      (node (ref "U10") (pin "2") (pinfunction "GAIN_SLOT_2") (pintype "unspecified"))
    )
    (net (code "33") (name "Net-(U10-OUTN)") (class "Default")
      (node (ref "SN") (pin "1") (pinfunction "1_1") (pintype "unspecified"))
      (node (ref "U10") (pin "10") (pinfunction "OUTN_10") (pintype "unspecified"))
    )
    (net (code "34") (name "Net-(U10-OUTP)") (class "Default")
      (node (ref "SP") (pin "1") (pinfunction "1_1") (pintype "unspecified"))
      (node (ref "U10") (pin "9") (pinfunction "OUTP_9") (pintype "unspecified"))
    )
    (net (code "35") (name "Net-(U10-SD_MODE#)") (class "Default")
      (node (ref "R22") (pin "1") (pinfunction "1_1") (pintype "input"))
      (node (ref "U10") (pin "4") (pinfunction "SD_MODE#_4") (pintype "unspecified"))
    )
    (net (code "36") (name "Net-(U11-CHIPEN)") (class "Default")
      (node (ref "R25") (pin "1") (pinfunction "1_1") (pintype "input"))
      (node (ref "U11") (pin "4") (pinfunction "CHIPEN_4") (pintype "unspecified"))
    )
    (net (code "37") (name "Net-(U11-L{slash}R)") (class "Default")
      (node (ref "R26") (pin "2") (pinfunction "2_2") (pintype "input"))
      (node (ref "U11") (pin "5") (pinfunction "L/R_5") (pintype "unspecified"))
    )
    (net (code "38") (name "Net-(U14-EN)") (class "Default")
      (node (ref "R36") (pin "1") (pinfunction "1_1") (pintype "input"))
      (node (ref "U14") (pin "1") (pinfunction "EN_1") (pintype "unspecified"))
    )
    (net (code "39") (name "Net-(U14-FB)") (class "Default")
      (node (ref "R37") (pin "2") (pinfunction "2_2") (pintype "input"))
      (node (ref "R38") (pin "1") (pinfunction "1_1") (pintype "input"))
      (node (ref "U14") (pin "5") (pinfunction "FB_5") (pintype "unspecified"))
    )
    (net (code "40") (name "Net-(U14-SW)") (class "Default")
      (node (ref "L1") (pin "1") (pinfunction "1_1") (pintype "unspecified"))
      (node (ref "U14") (pin "3") (pinfunction "SW_3") (pintype "unspecified"))
    )
    (net (code "41") (name "Net-(USB1-CC1)") (class "Default")
      (node (ref "R24") (pin "1") (pinfunction "1_1") (pintype "input"))
      (node (ref "USB1") (pin "4") (pinfunction "CC1_4") (pintype "unspecified"))
    )
    (net (code "42") (name "Net-(USB1-CC2)") (class "Default")
      (node (ref "R23") (pin "2") (pinfunction "2_2") (pintype "input"))
      (node (ref "USB1") (pin "10") (pinfunction "CC2_10") (pintype "unspecified"))
    )
    (net (code "43") (name "RXD0") (class "Default")
      (node (ref "RXD0") (pin "1") (pinfunction "1_1") (pintype "input"))
      (node (ref "U1") (pin "50") (pinfunction "U0RXD_50") (pintype "unspecified"))
    )
    (net (code "44") (name "SPICLK") (class "Default")
      (node (ref "U1") (pin "33") (pinfunction "SPICLK_33") (pintype "unspecified"))
      (node (ref "U2") (pin "6") (pinfunction "CLK_6") (pintype "unspecified"))
    )
    (net (code "45") (name "SPICS0") (class "Default")
      (node (ref "U1") (pin "32") (pinfunction "SPICS0_32") (pintype "unspecified"))
      (node (ref "U2") (pin "1") (pinfunction "CS#_1") (pintype "unspecified"))
    )
    (net (code "46") (name "SPID") (class "Default")
      (node (ref "U1") (pin "35") (pinfunction "SPID_35") (pintype "unspecified"))
      (node (ref "U2") (pin "5") (pinfunction "DI(IO0)_5") (pintype "unspecified"))
    )
    (net (code "47") (name "SPIHD") (class "Default")
      (node (ref "U1") (pin "30") (pinfunction "SPIHD_30") (pintype "unspecified"))
      (node (ref "U2") (pin "7") (pinfunction "HOLD_or_RESET#（IO3）_7") (pintype "unspecified"))
    )
    (net (code "48") (name "SPIQ") (class "Default")
      (node (ref "U1") (pin "34") (pinfunction "SPIQ_34") (pintype "unspecified"))
      (node (ref "U2") (pin "2") (pinfunction "DO(IO1)_2") (pintype "unspecified"))
    )
    (net (code "49") (name "SPIWP") (class "Default")
      (node (ref "U1") (pin "31") (pinfunction "SPIWP_31") (pintype "unspecified"))
      (node (ref "U2") (pin "3") (pinfunction "WP(IO2)#_3") (pintype "unspecified"))
    )
    (net (code "50") (name "SPI_CS_LCD") (class "Default")
      (node (ref "FPC2") (pin "8") (pinfunction "8_8") (pintype "input"))
      (node (ref "U1") (pin "10") (pinfunction "GPIO5_10") (pintype "unspecified"))
    )
    (net (code "51") (name "SPI_DC_LCD") (class "Default")
      (node (ref "FPC2") (pin "7") (pinfunction "7_7") (pintype "input"))
      (node (ref "U1") (pin "9") (pinfunction "GPIO4_9") (pintype "unspecified"))
    )
    (net (code "52") (name "SPI_MOSI") (class "Default")
      (node (ref "FPC2") (pin "10") (pinfunction "10_10") (pintype "input"))
      (node (ref "U1") (pin "12") (pinfunction "GPIO7_12") (pintype "unspecified"))
    )
    (net (code "53") (name "SPI_RST_LCD") (class "Default")
      (node (ref "FPC2") (pin "11") (pinfunction "11_11") (pintype "input"))
      (node (ref "U1") (pin "13") (pinfunction "GPIO8_13") (pintype "unspecified"))
    )
    (net (code "54") (name "SPI_SCK") (class "Default")
      (node (ref "FPC2") (pin "9") (pinfunction "9_9") (pintype "input"))
      (node (ref "U1") (pin "11") (pinfunction "GPIO6_11") (pintype "unspecified"))
    )
    (net (code "55") (name "TP_INT") (class "Default")
      (node (ref "FPC2") (pin "16") (pinfunction "16_16") (pintype "input"))
      (node (ref "U1") (pin "18") (pinfunction "GPIO13_18") (pintype "unspecified"))
    )
    (net (code "56") (name "TP_RST") (class "Default")
      (node (ref "FPC2") (pin "15") (pinfunction "15_15") (pintype "input"))
      (node (ref "U1") (pin "19") (pinfunction "GPIO14_19") (pintype "unspecified"))
    )
    (net (code "57") (name "TXD0") (class "Default")
      (node (ref "TXD0") (pin "1") (pinfunction "1_1") (pintype "input"))
      (node (ref "U1") (pin "49") (pinfunction "U0TXD_49") (pintype "unspecified"))
    )
    (net (code "58") (name "VBAT") (class "Default")
      (node (ref "C27") (pin "1") (pinfunction "1_1") (pintype "unspecified"))
      (node (ref "C28") (pin "1") (pinfunction "1_1") (pintype "unspecified"))
      (node (ref "C54") (pin "2") (pinfunction "2_2") (pintype "unspecified"))
      (node (ref "R33") (pin "1") (pinfunction "1_1") (pintype "input"))
      (node (ref "R34") (pin "2") (pinfunction "2_2") (pintype "input"))
      (node (ref "U12") (pin "2") (pinfunction "CELL_2") (pintype "unspecified"))
      (node (ref "U12") (pin "3") (pinfunction "VDD_3") (pintype "unspecified"))
      (node (ref "U13") (pin "1") (pinfunction "1_1") (pintype "unspecified"))
      (node (ref "U9") (pin "2") (pinfunction "2_2") (pintype "unspecified"))
    )
    (net (code "59") (name "VBUS") (class "Default")
      (node (ref "C24") (pin "1") (pinfunction "1_1") (pintype "unspecified"))
      (node (ref "C29") (pin "2") (pinfunction "2_2") (pintype "unspecified"))
      (node (ref "U8") (pin "1") (pinfunction "VIN_1") (pintype "unspecified"))
      (node (ref "USB1") (pin "11") (pinfunction "VBUS_11") (pintype "unspecified"))
      (node (ref "USB1") (pin "2") (pinfunction "VBUS_2") (pintype "unspecified"))
    )
    (net (code "60") (name "VDD33") (class "Default")
      (node (ref "C10") (pin "2") (pinfunction "2_2") (pintype "unspecified"))
      (node (ref "C16") (pin "2") (pinfunction "2_2") (pintype "unspecified"))
      (node (ref "C23") (pin "2") (pinfunction "2_2") (pintype "unspecified"))
      (node (ref "C30") (pin "2") (pinfunction "2_2") (pintype "unspecified"))
      (node (ref "C34") (pin "2") (pinfunction "2_2") (pintype "unspecified"))
      (node (ref "C36") (pin "2") (pinfunction "2_2") (pintype "unspecified"))
      (node (ref "C49") (pin "2") (pinfunction "2_2") (pintype "unspecified"))
      (node (ref "C50") (pin "2") (pinfunction "2_2") (pintype "unspecified"))
      (node (ref "C51") (pin "2") (pinfunction "2_2") (pintype "unspecified"))
      (node (ref "C52") (pin "2") (pinfunction "2_2") (pintype "unspecified"))
      (node (ref "C56") (pin "2") (pinfunction "2_2") (pintype "unspecified"))
      (node (ref "C57") (pin "2") (pinfunction "2_2") (pintype "unspecified"))
      (node (ref "C58") (pin "1") (pinfunction "1_1") (pintype "unspecified"))
      (node (ref "C59") (pin "1") (pinfunction "1_1") (pintype "unspecified"))
      (node (ref "C6") (pin "2") (pinfunction "2_2") (pintype "unspecified"))
      (node (ref "C7") (pin "2") (pinfunction "2_2") (pintype "unspecified"))
      (node (ref "C8") (pin "2") (pinfunction "2_2") (pintype "unspecified"))
      (node (ref "FPC2") (pin "17") (pinfunction "17_17") (pintype "input"))
      (node (ref "FPC2") (pin "3") (pinfunction "3_3") (pintype "input"))
      (node (ref "FPC2") (pin "4") (pinfunction "4_4") (pintype "input"))
      (node (ref "L1") (pin "2") (pinfunction "2_2") (pintype "unspecified"))
      (node (ref "R22") (pin "2") (pinfunction "2_2") (pintype "input"))
      (node (ref "R25") (pin "2") (pinfunction "2_2") (pintype "input"))
      (node (ref "R29") (pin "2") (pinfunction "2_2") (pintype "input"))
      (node (ref "R30") (pin "2") (pinfunction "2_2") (pintype "input"))
      (node (ref "R32") (pin "2") (pinfunction "2_2") (pintype "input"))
      (node (ref "R37") (pin "1") (pinfunction "1_1") (pintype "input"))
      (node (ref "R39") (pin "2") (pinfunction "2_2") (pintype "input"))
      (node (ref "R6") (pin "2") (pinfunction "2_2") (pintype "input"))
      (node (ref "R7") (pin "2") (pinfunction "2_2") (pintype "input"))
      (node (ref "U1") (pin "2") (pinfunction "VDD3P3_2") (pintype "unspecified"))
      (node (ref "U1") (pin "20") (pinfunction "VDD3P3_RTC_20") (pintype "unspecified"))
      (node (ref "U1") (pin "3") (pinfunction "VDD3P3_3") (pintype "unspecified"))
      (node (ref "U1") (pin "46") (pinfunction "VDD3P3_CPU_46") (pintype "unspecified"))
      (node (ref "U1") (pin "55") (pinfunction "VDDA_55") (pintype "unspecified"))
      (node (ref "U1") (pin "56") (pinfunction "VDDA_56") (pintype "unspecified"))
      (node (ref "U10") (pin "7") (pinfunction "VDD_7") (pintype "unspecified"))
      (node (ref "U10") (pin "8") (pinfunction "VDD_8") (pintype "unspecified"))
      (node (ref "U11") (pin "8") (pinfunction "VDD_8") (pintype "unspecified"))
    )
    (net (code "61") (name "VDD_SPI") (class "Default")
      (node (ref "C2") (pin "2") (pinfunction "2_2") (pintype "unspecified"))
      (node (ref "C35") (pin "2") (pinfunction "2_2") (pintype "unspecified"))
      (node (ref "U1") (pin "29") (pinfunction "VDD_SPI_29") (pintype "unspecified"))
      (node (ref "U2") (pin "8") (pinfunction "VCC_8") (pintype "unspecified"))
    )
    (net (code "62") (name "VSYS") (class "Default")
      (node (ref "C25") (pin "1") (pinfunction "1_1") (pintype "unspecified"))
      (node (ref "C53") (pin "2") (pinfunction "2_2") (pintype "unspecified"))
      (node (ref "C60") (pin "2") (pinfunction "2_2") (pintype "unspecified"))
      (node (ref "R36") (pin "2") (pinfunction "2_2") (pintype "input"))
      (node (ref "U14") (pin "4") (pinfunction "VIN_4") (pintype "unspecified"))
      (node (ref "U8") (pin "8") (pinfunction "VOUT_8") (pintype "unspecified"))
      (node (ref "WS") (pin "4") (pinfunction "VDD_4") (pintype "unspecified"))
    )
    (net (code "63") (name "WS2812") (class "Default")
      (node (ref "U1") (pin "16") (pinfunction "GPIO11_16") (pintype "unspecified"))
      (node (ref "WS") (pin "3") (pinfunction "DI_3") (pintype "unspecified"))
    )
    (net (code "64") (name "XTAL_N") (class "Default")
      (node (ref "C4") (pin "1") (pinfunction "1_1") (pintype "unspecified"))
      (node (ref "U1") (pin "53") (pinfunction "XTAL_N_53") (pintype "unspecified"))
      (node (ref "X1") (pin "3") (pinfunction "OSC2_3") (pintype "unspecified"))
    )
    (net (code "65") (name "XTAL_P") (class "Default")
      (node (ref "C3") (pin "2") (pinfunction "2_2") (pintype "unspecified"))
      (node (ref "U1") (pin "54") (pinfunction "XTAL_P_54") (pintype "unspecified"))
      (node (ref "X1") (pin "1") (pinfunction "OSC1_1") (pintype "unspecified"))
    )
    (net (code "66") (name "unconnected-(U1-GPIO18-Pad24)") (class "Default")
      (node (ref "U1") (pin "24") (pinfunction "GPIO18_24") (pintype "unspecified"))
    )
    (net (code "67") (name "unconnected-(U1-GPIO33-Pad38)") (class "Default")
      (node (ref "U1") (pin "38") (pinfunction "GPIO33_38") (pintype "unspecified+no_connect"))
    )
    (net (code "68") (name "unconnected-(U1-GPIO34-Pad39)") (class "Default")
      (node (ref "U1") (pin "39") (pinfunction "GPIO34_39") (pintype "unspecified+no_connect"))
    )
    (net (code "69") (name "unconnected-(U1-GPIO35-Pad40)") (class "Default")
      (node (ref "U1") (pin "40") (pinfunction "GPIO35_40") (pintype "unspecified+no_connect"))
    )
    (net (code "70") (name "unconnected-(U1-GPIO36-Pad41)") (class "Default")
      (node (ref "U1") (pin "41") (pinfunction "GPIO36_41") (pintype "unspecified+no_connect"))
    )
    (net (code "71") (name "unconnected-(U1-GPIO37-Pad42)") (class "Default")
      (node (ref "U1") (pin "42") (pinfunction "GPIO37_42") (pintype "unspecified+no_connect"))
    )
    (net (code "72") (name "unconnected-(U1-SPICLK_N-Pad36)") (class "Default")
      (node (ref "U1") (pin "36") (pinfunction "SPICLK_N_36") (pintype "unspecified"))
    )
    (net (code "73") (name "unconnected-(U1-SPICS1-Pad28)") (class "Default")
      (node (ref "U1") (pin "28") (pinfunction "SPICS1_28") (pintype "unspecified+no_connect"))
    )
    (net (code "74") (name "unconnected-(U1-XTAL_32K_P-Pad21)") (class "Default")
      (node (ref "U1") (pin "21") (pinfunction "XTAL_32K_P_21") (pintype "unspecified"))
    )
    (net (code "75") (name "unconnected-(U3-Pad1)") (class "Default")
      (node (ref "U3") (pin "1") (pinfunction "1_1") (pintype "unspecified+no_connect"))
    )
    (net (code "76") (name "unconnected-(U8-KEY-Pad5)") (class "Default")
      (node (ref "U8") (pin "5") (pinfunction "KEY_5") (pintype "unspecified+no_connect"))
    )
    (net (code "77") (name "unconnected-(U10-N.C.-Pad5)") (class "Default")
      (node (ref "U10") (pin "5") (pinfunction "N.C._5") (pintype "unspecified+no_connect"))
    )
    (net (code "78") (name "unconnected-(U10-N.C.-Pad6)") (class "Default")
      (node (ref "U10") (pin "6") (pinfunction "N.C._6") (pintype "unspecified+no_connect"))
    )
    (net (code "79") (name "unconnected-(U10-N.C.-Pad12)") (class "Default")
      (node (ref "U10") (pin "12") (pinfunction "N.C._12") (pintype "unspecified+no_connect"))
    )
    (net (code "80") (name "unconnected-(U10-N.C.-Pad13)") (class "Default")
      (node (ref "U10") (pin "13") (pinfunction "N.C._13") (pintype "unspecified+no_connect"))
    )
    (net (code "81") (name "unconnected-(U11-N{slash}C-Pad2)") (class "Default")
      (node (ref "U11") (pin "2") (pinfunction "N/C_2") (pintype "unspecified+no_connect"))
    )
    (net (code "82") (name "unconnected-(USB1-SBU1-Pad9)") (class "Default")
      (node (ref "USB1") (pin "9") (pinfunction "SBU1_9") (pintype "unspecified+no_connect"))
    )
    (net (code "83") (name "unconnected-(USB1-SBU2-Pad3)") (class "Default")
      (node (ref "USB1") (pin "3") (pinfunction "SBU2_3") (pintype "unspecified+no_connect"))
    )
    (net (code "84") (name "unconnected-(WS-DO-Pad1)") (class "Default")
      (node (ref "WS") (pin "1") (pinfunction "DO_1") (pintype "unspecified+no_connect"))
    )
  )
)
